# Power.net
KiCad netlist of a schematic drawn in Altium Designer
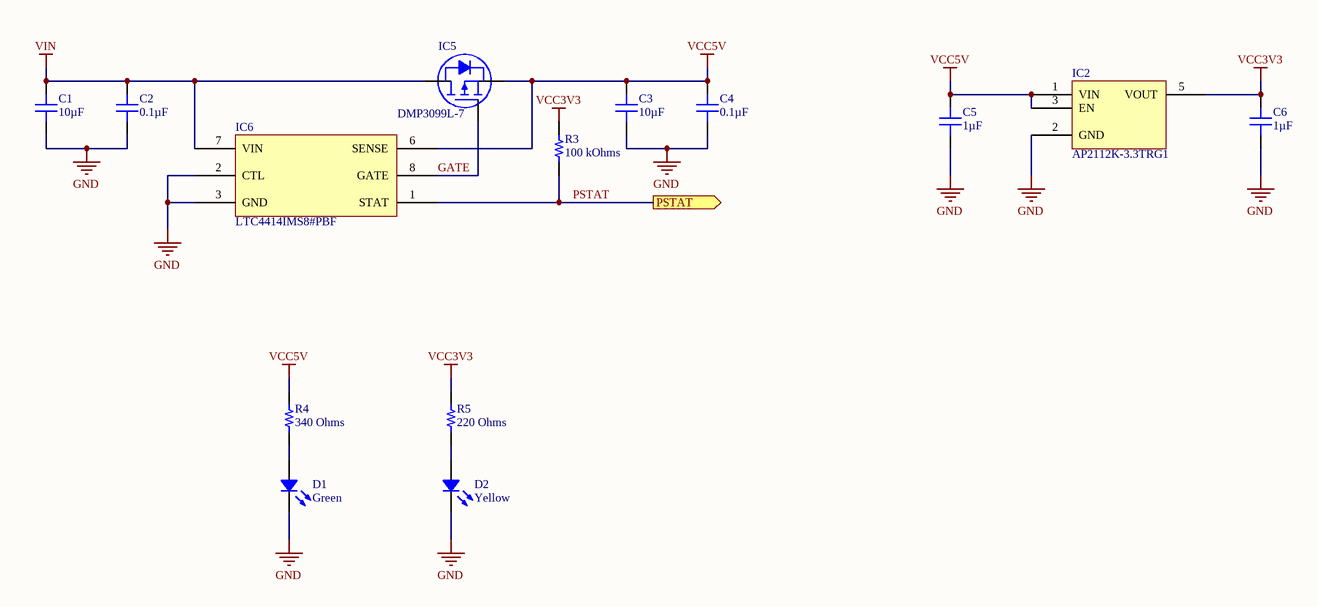
[diagram p0: Power.SchDoc]

(export (version "E")
  (design (tool "Eeschema 10.0.6"))
  (components
    (comp (ref "C1")
      (value "10µF")
      (footprint "CAP 0402_1005")
      (description "CAP CER 10UF 10V X5R 0402")
      (fields
        (field (name "PART NUMBER") "CL05A106MP8NUB8")
        (field (name "MANUFACTURER") "Samsung Electro-Mechanics")
      )
      (libsource (lib "Celestial") (part "Capacitor"))
    )
    (comp (ref "C2")
      (value "0.1µF")
      (footprint "CAP 0402_1005")
      (description "CAP CER 0402 0.1UF 16V X7R 10%")
      (fields (field (name "PART NUMBER") "C0402C104K4RECAUTO") (field (name "MANUFACTURER") "KEMET"))
      (libsource (lib "Celestial") (part "Capacitor"))
    )
    (comp (ref "C3")
      (value "10µF")
      (footprint "CAP 0402_1005")
      (description "CAP CER 10UF 10V X5R 0402")
      (fields
        (field (name "PART NUMBER") "CL05A106MP8NUB8")
        (field (name "MANUFACTURER") "Samsung Electro-Mechanics")
      )
      (libsource (lib "Celestial") (part "Capacitor"))
    )
    (comp (ref "C4")
      (value "0.1µF")
      (footprint "CAP 0402_1005")
      (description "CAP CER 0402 0.1UF 16V X7R 10%")
      (fields (field (name "PART NUMBER") "C0402C104K4RECAUTO") (field (name "MANUFACTURER") "KEMET"))
      (libsource (lib "Celestial") (part "Capacitor"))
    )
    (comp (ref "C5")
      (value "1µF")
      (footprint "CAP 0402_1005")
      (description "CAP CER 1UF 10V X5R 0402")
      (fields (field (name "PART NUMBER") "0402ZD105KAT4A") (field (name "MANUFACTURER") "AVX Corporation"))
      (libsource (lib "Celestial") (part "Capacitor"))
    )
    (comp (ref "C6")
      (value "1µF")
      (footprint "CAP 0402_1005")
      (description "CAP CER 1UF 10V X5R 0402")
      (fields (field (name "PART NUMBER") "0402ZD105KAT4A") (field (name "MANUFACTURER") "AVX Corporation"))
      (libsource (lib "Celestial") (part "Capacitor"))
    )
    (comp (ref "D1")
      (value "Green")
      (footprint "LED 0402_1005 GREEN")
      (description "LED GREEN CLEAR 2SMD")
      (fields
        (field (name "PART NUMBER") "EAST10052GA0")
        (field (name "MANUFACTURER") "Everlight Electronics Co Ltd")
      )
      (libsource (lib "Celestial") (part "LED"))
    )
    (comp (ref "D2")
      (value "Yellow")
      (footprint "LED 0402_1005 YELLOW")
      (description "LED YELLOW CLEAR CHIP SMD")
      (fields (field (name "PART NUMBER") "APG1005SYC-T") (field (name "MANUFACTURER") "Kingbright"))
      (libsource (lib "Celestial") (part "LED"))
    )
    (comp (ref "IC2")
      (value "AP2112K-3.3TRG1")
      (footprint "DIODES SOT-23-5 W5")
      (description "IC REG LINEAR 3.3V 600MA SOT25")
      (fields (field (name "MANUFACTURER") "Diodes Incorporated"))
      (libsource (lib "Celestial") (part "DIODES INC AP2112K"))
    )
    (comp (ref "IC5")
      (value "DMP3099L-7")
      (footprint "DIODES SOT-23-3")
      (description "MOSFET P-CH 30V SOT23")
      (fields (field (name "MANUFACTURER") "Diodes Incorporated"))
      (libsource (lib "Celestial") (part "DIODES MOSFET P-CH SOT-23-3"))
    )
    (comp (ref "IC6")
      (value "LTC4414IMS8#PBF")
      (footprint "ANALOG MSOP-8 RM-8")
      (description "IC OR CTRLR SRC SELECT 8MSOP")
      (fields (field (name "MANUFACTURER") "Linear Technology/Analog Devices"))
      (libsource (lib "Celestial") (part "ANALOG LTC4414"))
    )
    (comp (ref "R3")
      (value "100 kOhms")
      (footprint "RES 0201_0603")
      (description "RES SMD 100K OHM 1% 1/20W 0201")
      (fields
        (field (name "PART NUMBER") "CRG0201F100K")
        (field (name "MANUFACTURER") "TE Connectivity Passive Product")
      )
      (libsource (lib "Celestial") (part "Resistor"))
    )
    (comp (ref "R4")
      (value "340 Ohms")
      (footprint "RES 0402_1005")
      (description "RES 340 OHM 1% 1/16W 0402")
      (fields (field (name "PART NUMBER") "AC0402FR-07340RL") (field (name "MANUFACTURER") "Yageo"))
      (libsource (lib "Celestial") (part "Resistor"))
    )
    (comp (ref "R5")
      (value "220 Ohms")
      (footprint "RES 0402_1005")
      (description "RES SMD 220 OHM 1% 1/16W 0402")
      (fields (field (name "PART NUMBER") "AC0402FR-07220RL") (field (name "MANUFACTURER") "Yageo"))
      (libsource (lib "Celestial") (part "Resistor"))
    )
  )
  (nets
    (net (code "1") (name "/GATE") (class "Default")
      (node (ref "IC5") (pin "1") (pinfunction "G_1") (pintype "passive"))
      (node (ref "IC6") (pin "8") (pinfunction "GATE_8") (pintype "passive"))
    )
    (net (code "2") (name "/PSTAT") (class "Default")
      (node (ref "IC6") (pin "1") (pinfunction "STAT_1") (pintype "passive"))
      (node (ref "R3") (pin "1") (pinfunction "1_1") (pintype "passive"))
    )
    (net (code "3") (name "GND") (class "Default")
      (node (ref "C1") (pin "1") (pinfunction "1_1") (pintype "passive"))
      (node (ref "C2") (pin "1") (pinfunction "1_1") (pintype "passive"))
      (node (ref "C3") (pin "1") (pinfunction "1_1") (pintype "passive"))
      (node (ref "C4") (pin "1") (pinfunction "1_1") (pintype "passive"))
      (node (ref "C5") (pin "1") (pinfunction "1_1") (pintype "passive"))
      (node (ref "C6") (pin "1") (pinfunction "1_1") (pintype "passive"))
      (node (ref "D1") (pin "2") (pinfunction "2_2") (pintype "passive"))
      (node (ref "D2") (pin "2") (pinfunction "2_2") (pintype "passive"))
      (node (ref "IC2") (pin "2") (pinfunction "GND_2") (pintype "passive"))
      (node (ref "IC6") (pin "2") (pinfunction "CTL_2") (pintype "passive"))
      (node (ref "IC6") (pin "3") (pinfunction "GND_3") (pintype "passive"))
    )
    (net (code "4") (name "Net-(D1-Pad1)") (class "Default")
      (node (ref "D1") (pin "1") (pinfunction "1_1") (pintype "passive"))
      (node (ref "R4") (pin "1") (pinfunction "1_1") (pintype "passive"))
    )
    (net (code "5") (name "Net-(D2-Pad1)") (class "Default")
      (node (ref "D2") (pin "1") (pinfunction "1_1") (pintype "passive"))
      (node (ref "R5") (pin "1") (pinfunction "1_1") (pintype "passive"))
    )
    (net (code "6") (name "VCC3V3") (class "Default")
      (node (ref "C6") (pin "2") (pinfunction "2_2") (pintype "passive"))
      (node (ref "IC2") (pin "5") (pinfunction "VOUT_5") (pintype "passive"))
      (node (ref "R3") (pin "2") (pinfunction "2_2") (pintype "passive"))
      (node (ref "R5") (pin "2") (pinfunction "2_2") (pintype "passive"))
    )
    (net (code "7") (name "VCC5V") (class "Default")
      (node (ref "C3") (pin "2") (pinfunction "2_2") (pintype "passive"))
      (node (ref "C4") (pin "2") (pinfunction "2_2") (pintype "passive"))
      (node (ref "C5") (pin "2") (pinfunction "2_2") (pintype "passive"))
      (node (ref "IC2") (pin "1") (pinfunction "VIN_1") (pintype "passive"))
      (node (ref "IC2") (pin "3") (pinfunction "EN_3") (pintype "passive"))
      (node (ref "IC5") (pin "2") (pinfunction "S_2") (pintype "passive"))
      (node (ref "IC6") (pin "6") (pinfunction "SENSE_6") (pintype "passive"))
      (node (ref "R4") (pin "2") (pinfunction "2_2") (pintype "passive"))
    )
    (net (code "8") (name "VIN") (class "Default")
      (node (ref "C1") (pin "2") (pinfunction "2_2") (pintype "passive"))
      (node (ref "C2") (pin "2") (pinfunction "2_2") (pintype "passive"))
      (node (ref "IC5") (pin "3") (pinfunction "D_3") (pintype "passive"))
      (node (ref "IC6") (pin "7") (pinfunction "VIN_7") (pintype "passive"))
    )
  )
)
